# Connectors.net
KiCad netlist of a schematic drawn in Altium Designer
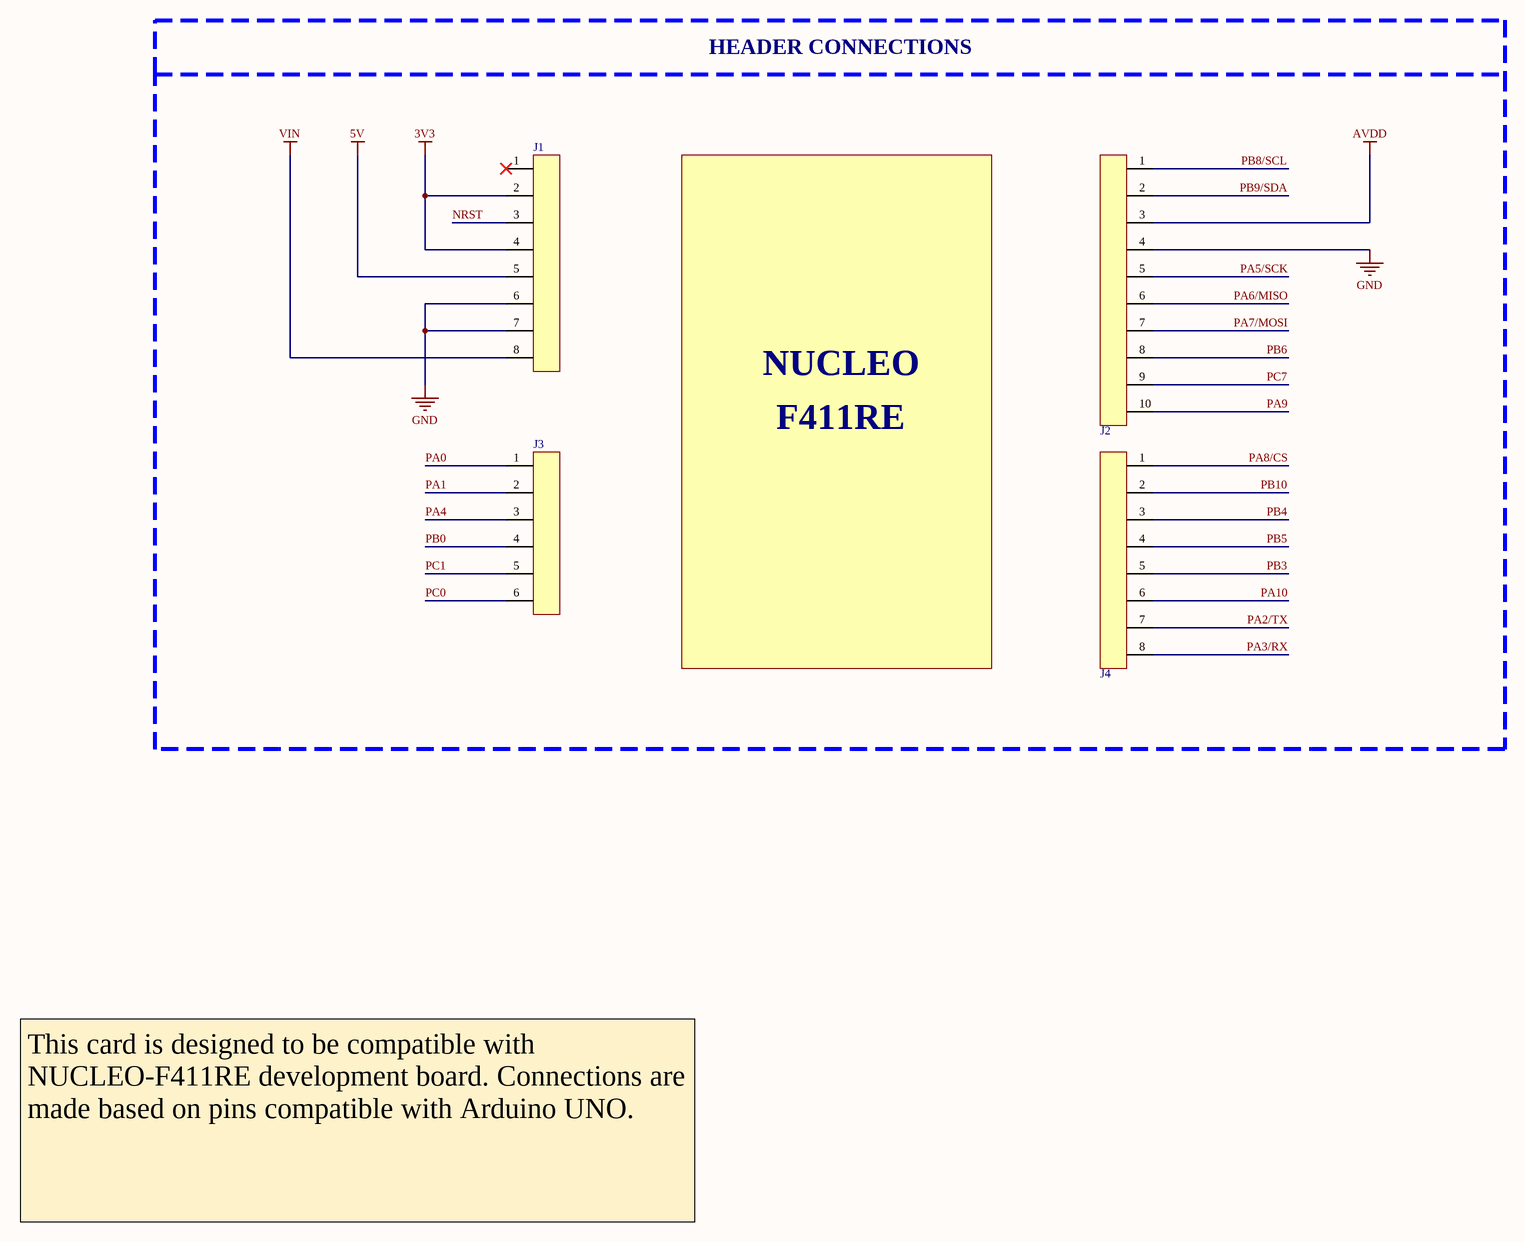
[diagram p0: Connectors.SchDoc]

(export (version "E")
  (design (tool "Eeschema 10.0.6"))
  (components
    (comp (ref "J1")
      (value "PPTC081LFBN-RC")
      (footprint "8x1 Female Header 2.54mm")
      (description "Female, 8C, Straight, .100\"CC; 3.20mm Tail, No Mt. 100u\" Tin; PBT, Phos Bronze, 105 C")
      (fields (field (name "MANUFACTURER") "Sullins") (field (name "DESIGNED BY") "Aslı Kurt"))
      (libsource (lib "") (part "8x1 Female Header 2.54mm_1"))
    )
    (comp (ref "J2")
      (value "PPTC101LFBN-RC")
      (footprint "10x1 Female Header 2.54mm")
      (description "10 Position Single Row 2.54 mm Pitch Vertical Through Hole Socket Header")
      (fields (field (name "MANUFACTURER") "Sullins") (field (name "DESIGNED BY") "Aslı Kurt"))
      (libsource (lib "Connectors") (part "10x1 Female Header 2.54mm"))
    )
    (comp (ref "J3")
      (value "PPTC061LFBN-RC")
      (footprint "6x1 Female Header 2.54mm")
      (description "Female, 6 C, Straight, .100\"CC; 3.20mm Tail, No Mt. 100u\" Tin; PBT, Phos Bronze, 105 C")
      (fields (field (name "MANUFACTURER") "Sullins") (field (name "DESIGNED BY") "Aslı Kurt"))
      (libsource (lib "Connectors") (part "6x1 Female Header 2.54mm"))
    )
    (comp (ref "J4")
      (value "PPTC081LFBN-RC")
      (footprint "8x1 Female Header 2.54mm")
      (description "Female, 8C, Straight, .100\"CC; 3.20mm Tail, No Mt. 100u\" Tin; PBT, Phos Bronze, 105 C")
      (fields (field (name "MANUFACTURER") "Sullins") (field (name "DESIGNED BY") "Aslı Kurt"))
      (libsource (lib "Connectors") (part "8x1 Female Header 2.54mm"))
    )
  )
  (nets
    (net (code "1") (name "/NRST") (class "Default")
      (node (ref "J1") (pin "3") (pinfunction "3_3") (pintype "power_in"))
    )
    (net (code "2") (name "/PA0") (class "Default")
      (node (ref "J3") (pin "1") (pinfunction "1_1") (pintype "power_in"))
    )
    (net (code "3") (name "/PA1") (class "Default")
      (node (ref "J3") (pin "2") (pinfunction "2_2") (pintype "power_in"))
    )
    (net (code "4") (name "/PA2{slash}TX") (class "Default")
      (node (ref "J4") (pin "7") (pinfunction "7_7") (pintype "passive"))
    )
    (net (code "5") (name "/PA3{slash}RX") (class "Default")
      (node (ref "J4") (pin "8") (pinfunction "8_8") (pintype "passive"))
    )
    (net (code "6") (name "/PA4") (class "Default")
      (node (ref "J3") (pin "3") (pinfunction "3_3") (pintype "power_in"))
    )
    (net (code "7") (name "/PA5{slash}SCK") (class "Default")
      (node (ref "J2") (pin "5") (pinfunction "5_5") (pintype "passive"))
    )
    (net (code "8") (name "/PA6{slash}MISO") (class "Default")
      (node (ref "J2") (pin "6") (pinfunction "6_6") (pintype "passive"))
    )
    (net (code "9") (name "/PA7{slash}MOSI") (class "Default")
      (node (ref "J2") (pin "7") (pinfunction "7_7") (pintype "passive"))
    )
    (net (code "10") (name "/PA8{slash}CS") (class "Default")
      (node (ref "J4") (pin "1") (pinfunction "1_1") (pintype "power_in"))
    )
    (net (code "11") (name "/PA9") (class "Default")
      (node (ref "J2") (pin "10") (pinfunction "10_10") (pintype "passive"))
    )
    (net (code "12") (name "/PA10") (class "Default")
      (node (ref "J4") (pin "6") (pinfunction "6_6") (pintype "passive"))
    )
    (net (code "13") (name "/PB0") (class "Default")
      (node (ref "J3") (pin "4") (pinfunction "4_4") (pintype "power_in"))
    )
    (net (code "14") (name "/PB3") (class "Default")
      (node (ref "J4") (pin "5") (pinfunction "5_5") (pintype "passive"))
    )
    (net (code "15") (name "/PB4") (class "Default")
      (node (ref "J4") (pin "3") (pinfunction "3_3") (pintype "power_in"))
    )
    (net (code "16") (name "/PB5") (class "Default")
      (node (ref "J4") (pin "4") (pinfunction "4_4") (pintype "power_in"))
    )
    (net (code "17") (name "/PB6") (class "Default")
      (node (ref "J2") (pin "8") (pinfunction "8_8") (pintype "passive"))
    )
    (net (code "18") (name "/PB8{slash}SCL") (class "Default")
      (node (ref "J2") (pin "1") (pinfunction "1_1") (pintype "power_in"))
    )
    (net (code "19") (name "/PB9{slash}SDA") (class "Default")
      (node (ref "J2") (pin "2") (pinfunction "2_2") (pintype "power_in"))
    )
    (net (code "20") (name "/PB10") (class "Default")
      (node (ref "J4") (pin "2") (pinfunction "2_2") (pintype "power_in"))
    )
    (net (code "21") (name "/PC0") (class "Default")
      (node (ref "J3") (pin "6") (pinfunction "6_6") (pintype "passive"))
    )
    (net (code "22") (name "/PC1") (class "Default")
      (node (ref "J3") (pin "5") (pinfunction "5_5") (pintype "passive"))
    )
    (net (code "23") (name "/PC7") (class "Default")
      (node (ref "J2") (pin "9") (pinfunction "9_9") (pintype "passive"))
    )
    (net (code "24") (name "3V3") (class "Default")
      (node (ref "J1") (pin "2") (pinfunction "2_2") (pintype "power_in"))
      (node (ref "J1") (pin "4") (pinfunction "4_4") (pintype "power_in"))
    )
    (net (code "25") (name "5V") (class "Default")
      (node (ref "J1") (pin "5") (pinfunction "5_5") (pintype "passive"))
    )
    (net (code "26") (name "AVDD") (class "Default")
      (node (ref "J2") (pin "3") (pinfunction "3_3") (pintype "power_in"))
    )
    (net (code "27") (name "GND") (class "Default")
      (node (ref "J1") (pin "6") (pinfunction "6_6") (pintype "passive"))
      (node (ref "J1") (pin "7") (pinfunction "7_7") (pintype "passive"))
      (node (ref "J2") (pin "4") (pinfunction "4_4") (pintype "power_in"))
    )
    (net (code "28") (name "VIN") (class "Default")
      (node (ref "J1") (pin "8") (pinfunction "8_8") (pintype "passive"))
    )
    (net (code "29") (name "unconnected-(J1-Pad1)") (class "Default")
      (node (ref "J1") (pin "1") (pinfunction "1_1") (pintype "power_in+no_connect"))
    )
  )
)
